# RPI_CM5_PINOUT.net
KiCad netlist of a schematic drawn in Altium Designer
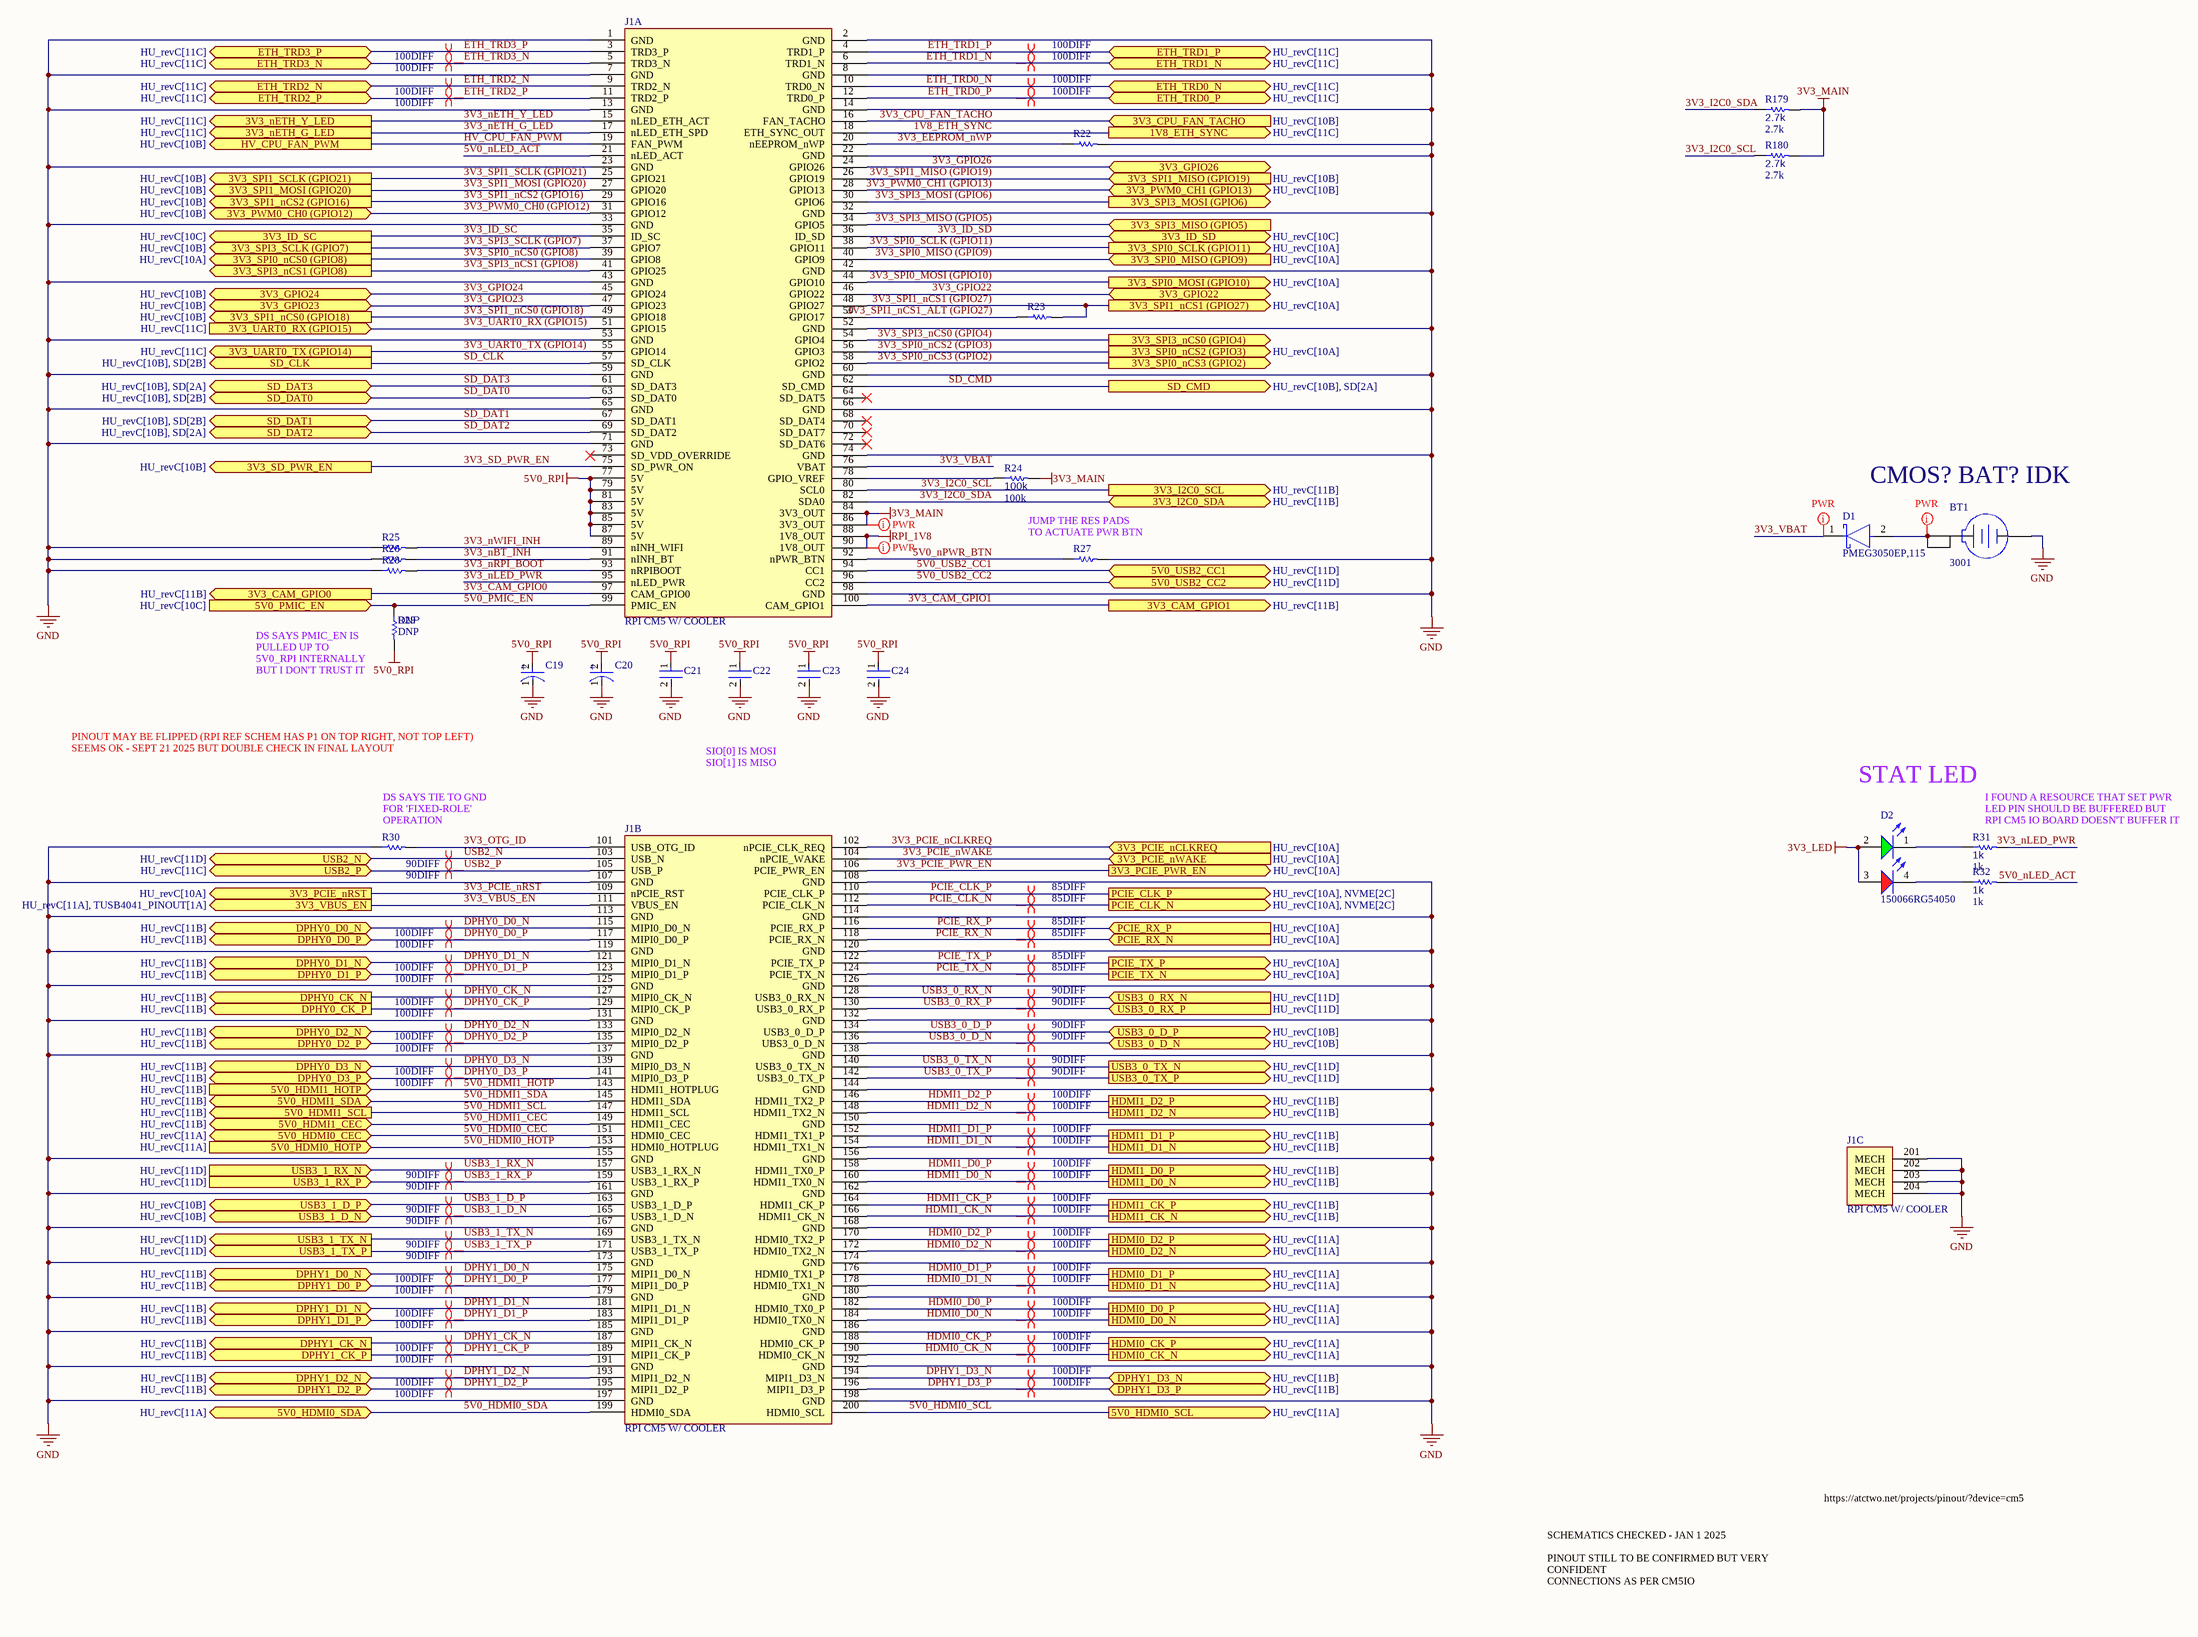
[diagram p0: RPI_CM5_PINOUT.SchDoc]

(export (version "E")
  (design (tool "Eeschema 10.0.6"))
  (components
    (comp (ref "BT1")
      (value "3001")
      (footprint "KSTN-3001_V")
      (description "Holder Battery Coin, 12 mm, 2-Pin THD, RoHS")
      (fields (field (name "MANUFACTURER") "Keystone"))
      (libsource (lib "Altium Content Vault") (part "BATTERY-HOLDER-COIN-3"))
    )
    (comp (ref "C19")
      (value "T491X107K025AT")
      (footprint "FP-T491X107K025AT-MFG")
      (description "CAP TANT 100UF 10% 25V 2917")
      (fields (field (name "TOLERANCE") "10%") (field (name "VOLTAGE") "25V"))
      (libsource (lib "Altium Content Vault") (part "cf48714ba7e38822c1575c7ec0b6d1f"))
    )
    (comp (ref "C20")
      (value "T491X107K025AT")
      (footprint "FP-T491X107K025AT-MFG")
      (description "CAP TANT 100UF 10% 25V 2917")
      (fields (field (name "TOLERANCE") "10%") (field (name "VOLTAGE") "25V"))
      (libsource (lib "Altium Content Vault") (part "cf48714ba7e38822c1575c7ec0b6d1f"))
    )
    (comp (ref "C21")
      (value "C3225X7R1H106M250AC")
      (footprint "FP-C3225-250-0_4-MFG")
      (description "Multilayer Ceramic Capacitors 10uF ±20% 50V X7R SMD 1210")
      (fields (field (name "TOLERANCE") "20%"))
      (libsource (lib "Altium Content Vault") (part "02cd4be3c70576c341d710602a673aa"))
    )
    (comp (ref "C22")
      (value "C3225X7R1H106M250AC")
      (footprint "FP-C3225-250-0_4-MFG")
      (description "Multilayer Ceramic Capacitors 10uF ±20% 50V X7R SMD 1210")
      (fields (field (name "TOLERANCE") "20%"))
      (libsource (lib "Altium Content Vault") (part "02cd4be3c70576c341d710602a673aa"))
    )
    (comp (ref "C23")
      (value "GRM21BR61E226ME44L")
      (footprint "FP-GRM21B-0_2-e0_2_0_7-IPC_B")
      (description "Chip Multilayer Ceramic Capacitors for General Purpose, 0805, 22uF, X5R, 15%, 20%, 25V")
      (fields (field (name "TOLERANCE") "20%") (field (name "VOLTAGE") "25V"))
      (libsource (lib "Altium Content Vault") (part "b4654b650e69147ec39a6b967a45e02"))
    )
    (comp (ref "C24")
      (value "GRM21BR61E226ME44L")
      (footprint "FP-GRM21B-0_2-e0_2_0_7-IPC_B")
      (description "Chip Multilayer Ceramic Capacitors for General Purpose, 0805, 22uF, X5R, 15%, 20%, 25V")
      (fields (field (name "TOLERANCE") "20%") (field (name "VOLTAGE") "25V"))
      (libsource (lib "Altium Content Vault") (part "b4654b650e69147ec39a6b967a45e02"))
    )
    (comp (ref "D1")
      (value "PMEG3050EP,115")
      (footprint "FP-SOD128-MFG")
      (description "DIODE SCHOTTKY 30V 5A SOD128")
      (libsource (lib "Altium Content Vault") (part "1d6ec82d83fb6aee721767c19dac4b9"))
    )
    (comp (ref "D2")
      (value "150066RG54050")
      (footprint "WL-SBCD_0606")
      (description "Led, Red/Grn, 180Mcd/230Mcd, 624Nm/525Nm Rohs Compliant: Yes")
      (fields (field (name "SOURCE") "rgled.SchLib"))
      (libsource (lib "Space Concordia") (part "CMP-004-00034-2"))
    )
    (comp (ref "J1")
      (value "RPI CM5 W/ COOLER")
      (footprint "RPI CM5 W_ COOLER-Footprint-1")
      (description "Mechanical placeholder for RPI CM5 w/ active cooler on it")
      (libsource (lib "Space Concordia") (part "10164227-1001A1RLF"))
    )
    (comp (ref "R22")
      (value "DNP")
      (footprint "RESC1005X40X25ML05T05")
      (description "READ THE NAME")
      (libsource (lib "Space Concordia") (part "CMP-009-00206-2"))
    )
    (comp (ref "R23")
      (value "DNP")
      (footprint "RESC1005X40X25ML05T05")
      (description "READ THE NAME")
      (libsource (lib "Space Concordia") (part "CMP-009-00206-2"))
    )
    (comp (ref "R24")
      (value "100k")
      (footprint "R0603B")
      (description "Resistor")
      (fields (field (name "ALTIUM_VALUE") "100k"))
      (libsource (lib "Space Concordia") (part "Resistor"))
    )
    (comp (ref "R25")
      (value "DNP")
      (footprint "RESC1005X40X25ML05T05")
      (description "READ THE NAME")
      (libsource (lib "Space Concordia") (part "CMP-009-00206-2"))
    )
    (comp (ref "R26")
      (value "DNP")
      (footprint "RESC1005X40X25ML05T05")
      (description "READ THE NAME")
      (libsource (lib "Space Concordia") (part "CMP-009-00206-2"))
    )
    (comp (ref "R27")
      (value "DNP")
      (footprint "RESC1005X40X25ML05T05")
      (description "READ THE NAME")
      (libsource (lib "Space Concordia") (part "CMP-009-00206-2"))
    )
    (comp (ref "R28")
      (value "DNP")
      (footprint "RESC1005X40X25ML05T05")
      (description "READ THE NAME")
      (libsource (lib "Space Concordia") (part "CMP-009-00206-2"))
    )
    (comp (ref "R29")
      (value "DNP")
      (footprint "R0603B")
      (description "Resistor")
      (fields (field (name "ALTIUM_VALUE") "DNP"))
      (libsource (lib "Space Concordia") (part "Resistor"))
    )
    (comp (ref "R30")
      (value "DNP")
      (footprint "RESC1005X40X25ML05T05")
      (description "READ THE NAME")
      (libsource (lib "Space Concordia") (part "CMP-009-00206-2"))
    )
    (comp (ref "R31")
      (value "1k")
      (footprint "R0603B")
      (description "Resistor")
      (fields (field (name "ALTIUM_VALUE") "1k"))
      (libsource (lib "Space Concordia") (part "Resistor"))
    )
    (comp (ref "R32")
      (value "1k")
      (footprint "R0603B")
      (description "Resistor")
      (fields (field (name "ALTIUM_VALUE") "1k"))
      (libsource (lib "Space Concordia") (part "Resistor"))
    )
    (comp (ref "R179")
      (value "2.7k")
      (footprint "R0603B")
      (description "Resistor")
      (fields (field (name "ALTIUM_VALUE") "2.7k"))
      (libsource (lib "Space Concordia") (part "Resistor"))
    )
    (comp (ref "R180")
      (value "2.7k")
      (footprint "R0603B")
      (description "Resistor")
      (fields (field (name "ALTIUM_VALUE") "2.7k"))
      (libsource (lib "Space Concordia") (part "Resistor"))
    )
  )
  (nets
    (net (code "1") (name "/1V8_ETH_SYNC") (class "Default")
      (node (ref "J1") (pin "18") (pinfunction "ETH_SYNC_OUT_18") (pintype "passive"))
    )
    (net (code "2") (name "/3V3_CAM_GPIO0") (class "Default")
      (node (ref "J1") (pin "97") (pinfunction "CAM_GPIO0_97") (pintype "passive"))
    )
    (net (code "3") (name "/3V3_CAM_GPIO1") (class "Default")
      (node (ref "J1") (pin "100") (pinfunction "CAM_GPIO1_100") (pintype "passive"))
    )
    (net (code "4") (name "/3V3_CPU_FAN_TACHO") (class "Default")
      (node (ref "J1") (pin "16") (pinfunction "FAN_TACHO_16") (pintype "passive"))
    )
    (net (code "5") (name "/3V3_EEPROM_nWP") (class "Default")
      (node (ref "J1") (pin "20") (pinfunction "nEEPROM_nWP_20") (pintype "passive"))
      (node (ref "R22") (pin "1") (pinfunction "1_1") (pintype "passive"))
    )
    (net (code "6") (name "/3V3_GPIO22") (class "Default")
      (node (ref "J1") (pin "46") (pinfunction "GPIO22_46") (pintype "passive"))
    )
    (net (code "7") (name "/3V3_GPIO23") (class "Default")
      (node (ref "J1") (pin "47") (pinfunction "GPIO23_47") (pintype "passive"))
    )
    (net (code "8") (name "/3V3_GPIO24") (class "Default")
      (node (ref "J1") (pin "45") (pinfunction "GPIO24_45") (pintype "passive"))
    )
    (net (code "9") (name "/3V3_GPIO26") (class "Default")
      (node (ref "J1") (pin "24") (pinfunction "GPIO26_24") (pintype "passive"))
    )
    (net (code "10") (name "/3V3_I2C0_SCL") (class "Default")
      (node (ref "J1") (pin "80") (pinfunction "SCL0_80") (pintype "passive"))
      (node (ref "R180") (pin "1") (pinfunction "1_1") (pintype "passive"))
    )
    (net (code "11") (name "/3V3_I2C0_SDA") (class "Default")
      (node (ref "J1") (pin "82") (pinfunction "SDA0_82") (pintype "passive"))
      (node (ref "R179") (pin "1") (pinfunction "1_1") (pintype "passive"))
    )
    (net (code "12") (name "/3V3_ID_SC") (class "Default")
      (node (ref "J1") (pin "35") (pinfunction "ID_SC_35") (pintype "passive"))
    )
    (net (code "13") (name "/3V3_ID_SD") (class "Default")
      (node (ref "J1") (pin "36") (pinfunction "ID_SD_36") (pintype "passive"))
    )
    (net (code "14") (name "/3V3_OTG_ID") (class "Default")
      (node (ref "J1") (pin "101") (pinfunction "USB_OTG_ID_101") (pintype "passive"))
      (node (ref "R30") (pin "2") (pinfunction "2_2") (pintype "passive"))
    )
    (net (code "15") (name "/3V3_PCIE_PWR_EN") (class "Default")
      (node (ref "J1") (pin "106") (pinfunction "PCIE_PWR_EN_106") (pintype "passive"))
    )
    (net (code "16") (name "/3V3_PCIE_nCLKREQ") (class "Default")
      (node (ref "J1") (pin "102") (pinfunction "nPCIE_CLK_REQ_102") (pintype "passive"))
    )
    (net (code "17") (name "/3V3_PCIE_nRST") (class "Default")
      (node (ref "J1") (pin "109") (pinfunction "nPCIE_RST_109") (pintype "passive"))
    )
    (net (code "18") (name "/3V3_PCIE_nWAKE") (class "Default")
      (node (ref "J1") (pin "104") (pinfunction "nPCIE_WAKE_104") (pintype "passive"))
    )
    (net (code "19") (name "/3V3_PWM0_CH0 (GPIO12)") (class "Default")
      (node (ref "J1") (pin "31") (pinfunction "GPIO12_31") (pintype "passive"))
    )
    (net (code "20") (name "/3V3_PWM0_CH1 (GPIO13)") (class "Default")
      (node (ref "J1") (pin "28") (pinfunction "GPIO13_28") (pintype "passive"))
    )
    (net (code "21") (name "/3V3_SD_PWR_EN") (class "Default")
      (node (ref "J1") (pin "75") (pinfunction "SD_PWR_ON_75") (pintype "passive"))
    )
    (net (code "22") (name "/3V3_SPI0_MISO (GPIO9)") (class "Default")
      (node (ref "J1") (pin "40") (pinfunction "GPIO9_40") (pintype "passive"))
    )
    (net (code "23") (name "/3V3_SPI0_MOSI (GPIO10)") (class "Default")
      (node (ref "J1") (pin "44") (pinfunction "GPIO10_44") (pintype "passive"))
    )
    (net (code "24") (name "/3V3_SPI0_SCLK (GPIO11)") (class "Default")
      (node (ref "J1") (pin "38") (pinfunction "GPIO11_38") (pintype "passive"))
    )
    (net (code "25") (name "/3V3_SPI0_nCS0 (GPIO8)") (class "Default")
      (node (ref "J1") (pin "39") (pinfunction "GPIO8_39") (pintype "passive"))
    )
    (net (code "26") (name "/3V3_SPI0_nCS2 (GPIO3)") (class "Default")
      (node (ref "J1") (pin "56") (pinfunction "GPIO3_56") (pintype "passive"))
    )
    (net (code "27") (name "/3V3_SPI0_nCS3 (GPIO2)") (class "Default")
      (node (ref "J1") (pin "58") (pinfunction "GPIO2_58") (pintype "passive"))
    )
    (net (code "28") (name "/3V3_SPI1_MISO (GPIO19)") (class "Default")
      (node (ref "J1") (pin "26") (pinfunction "GPIO19_26") (pintype "passive"))
    )
    (net (code "29") (name "/3V3_SPI1_MOSI (GPIO20)") (class "Default")
      (node (ref "J1") (pin "27") (pinfunction "GPIO20_27") (pintype "passive"))
    )
    (net (code "30") (name "/3V3_SPI1_SCLK (GPIO21)") (class "Default")
      (node (ref "J1") (pin "25") (pinfunction "GPIO21_25") (pintype "passive"))
    )
    (net (code "31") (name "/3V3_SPI1_nCS0 (GPIO18)") (class "Default")
      (node (ref "J1") (pin "49") (pinfunction "GPIO18_49") (pintype "passive"))
    )
    (net (code "32") (name "/3V3_SPI1_nCS1 (GPIO27)") (class "Default")
      (node (ref "J1") (pin "48") (pinfunction "GPIO27_48") (pintype "passive"))
      (node (ref "R23") (pin "2") (pinfunction "2_2") (pintype "passive"))
    )
    (net (code "33") (name "/3V3_SPI1_nCS1_ALT (GPIO27)") (class "Default")
      (node (ref "J1") (pin "50") (pinfunction "GPIO17_50") (pintype "passive"))
      (node (ref "R23") (pin "1") (pinfunction "1_1") (pintype "passive"))
    )
    (net (code "34") (name "/3V3_SPI1_nCS2 (GPIO16)") (class "Default")
      (node (ref "J1") (pin "29") (pinfunction "GPIO16_29") (pintype "passive"))
    )
    (net (code "35") (name "/3V3_SPI3_MISO (GPIO5)") (class "Default")
      (node (ref "J1") (pin "34") (pinfunction "GPIO5_34") (pintype "passive"))
    )
    (net (code "36") (name "/3V3_SPI3_MOSI (GPIO6)") (class "Default")
      (node (ref "J1") (pin "30") (pinfunction "GPIO6_30") (pintype "passive"))
    )
    (net (code "37") (name "/3V3_SPI3_SCLK (GPIO7)") (class "Default")
      (node (ref "J1") (pin "37") (pinfunction "GPIO7_37") (pintype "passive"))
    )
    (net (code "38") (name "/3V3_SPI3_nCS0 (GPIO4)") (class "Default")
      (node (ref "J1") (pin "54") (pinfunction "GPIO4_54") (pintype "passive"))
    )
    (net (code "39") (name "/3V3_SPI3_nCS1 (GPIO8)") (class "Default")
      (node (ref "J1") (pin "41") (pinfunction "GPIO25_41") (pintype "passive"))
    )
    (net (code "40") (name "/3V3_UART0_RX (GPIO15)") (class "Default")
      (node (ref "J1") (pin "51") (pinfunction "GPIO15_51") (pintype "passive"))
    )
    (net (code "41") (name "/3V3_UART0_TX (GPIO14)") (class "Default")
      (node (ref "J1") (pin "55") (pinfunction "GPIO14_55") (pintype "passive"))
    )
    (net (code "42") (name "/3V3_VBAT") (class "Default")
      (node (ref "D1") (pin "1") (pinfunction "C_1") (pintype "passive"))
      (node (ref "J1") (pin "76") (pinfunction "VBAT_76") (pintype "passive"))
    )
    (net (code "43") (name "/3V3_VBUS_EN") (class "Default")
      (node (ref "J1") (pin "111") (pinfunction "VBUS_EN_111") (pintype "passive"))
    )
    (net (code "44") (name "/3V3_nBT_INH") (class "Default")
      (node (ref "J1") (pin "91") (pinfunction "nINH_BT_91") (pintype "passive"))
      (node (ref "R26") (pin "2") (pinfunction "2_2") (pintype "passive"))
    )
    (net (code "45") (name "/3V3_nETH_G_LED") (class "Default")
      (node (ref "J1") (pin "17") (pinfunction "nLED_ETH_SPD_17") (pintype "passive"))
    )
    (net (code "46") (name "/3V3_nETH_Y_LED") (class "Default")
      (node (ref "J1") (pin "15") (pinfunction "nLED_ETH_ACT_15") (pintype "passive"))
    )
    (net (code "47") (name "/3V3_nLED_PWR") (class "Default")
      (node (ref "J1") (pin "95") (pinfunction "nLED_PWR_95") (pintype "passive"))
      (node (ref "R31") (pin "2") (pinfunction "2_2") (pintype "passive"))
    )
    (net (code "48") (name "/3V3_nRPI_BOOT") (class "Default")
      (node (ref "J1") (pin "93") (pinfunction "nRPIBOOT_93") (pintype "passive"))
      (node (ref "R28") (pin "2") (pinfunction "2_2") (pintype "passive"))
    )
    (net (code "49") (name "/3V3_nWIFI_INH") (class "Default")
      (node (ref "J1") (pin "89") (pinfunction "nINH_WIFI_89") (pintype "passive"))
      (node (ref "R25") (pin "2") (pinfunction "2_2") (pintype "passive"))
    )
    (net (code "50") (name "/5V0_HDMI0_CEC") (class "Default")
      (node (ref "J1") (pin "151") (pinfunction "HDMI0_CEC_151") (pintype "passive"))
    )
    (net (code "51") (name "/5V0_HDMI0_HOTP") (class "Default")
      (node (ref "J1") (pin "153") (pinfunction "HDMI0_HOTPLUG_153") (pintype "passive"))
    )
    (net (code "52") (name "/5V0_HDMI0_SCL") (class "Default")
      (node (ref "J1") (pin "200") (pinfunction "HDMI0_SCL_200") (pintype "passive"))
    )
    (net (code "53") (name "/5V0_HDMI0_SDA") (class "Default")
      (node (ref "J1") (pin "199") (pinfunction "HDMI0_SDA_199") (pintype "passive"))
    )
    (net (code "54") (name "/5V0_HDMI1_CEC") (class "Default")
      (node (ref "J1") (pin "149") (pinfunction "HDMI1_CEC_149") (pintype "passive"))
    )
    (net (code "55") (name "/5V0_HDMI1_HOTP") (class "Default")
      (node (ref "J1") (pin "143") (pinfunction "HDMI1_HOTPLUG_143") (pintype "passive"))
    )
    (net (code "56") (name "/5V0_HDMI1_SCL") (class "Default")
      (node (ref "J1") (pin "147") (pinfunction "HDMI1_SCL_147") (pintype "passive"))
    )
    (net (code "57") (name "/5V0_HDMI1_SDA") (class "Default")
      (node (ref "J1") (pin "145") (pinfunction "HDMI1_SDA_145") (pintype "passive"))
    )
    (net (code "58") (name "/5V0_PMIC_EN") (class "Default")
      (node (ref "J1") (pin "99") (pinfunction "PMIC_EN_99") (pintype "passive"))
      (node (ref "R29") (pin "1") (pinfunction "1_1") (pintype "passive"))
    )
    (net (code "59") (name "/5V0_USB2_CC1") (class "Default")
      (node (ref "J1") (pin "94") (pinfunction "CC1_94") (pintype "passive"))
    )
    (net (code "60") (name "/5V0_USB2_CC2") (class "Default")
      (node (ref "J1") (pin "96") (pinfunction "CC2_96") (pintype "passive"))
    )
    (net (code "61") (name "/5V0_nLED_ACT") (class "Default")
      (node (ref "J1") (pin "21") (pinfunction "nLED_ACT_21") (pintype "passive"))
      (node (ref "R32") (pin "2") (pinfunction "2_2") (pintype "passive"))
    )
    (net (code "62") (name "/5V0_nPWR_BTN") (class "Default")
      (node (ref "J1") (pin "92") (pinfunction "nPWR_BTN_92") (pintype "passive"))
      (node (ref "R27") (pin "1") (pinfunction "1_1") (pintype "passive"))
    )
    (net (code "63") (name "/DPHY0_CK_N") (class "Default")
      (node (ref "J1") (pin "127") (pinfunction "MIPI0_CK_N_127") (pintype "passive"))
    )
    (net (code "64") (name "/DPHY0_CK_P") (class "Default")
      (node (ref "J1") (pin "129") (pinfunction "MIPI0_CK_P_129") (pintype "passive"))
    )
    (net (code "65") (name "/DPHY0_D0_N") (class "Default")
      (node (ref "J1") (pin "115") (pinfunction "MIPI0_D0_N_115") (pintype "passive"))
    )
    (net (code "66") (name "/DPHY0_D0_P") (class "Default")
      (node (ref "J1") (pin "117") (pinfunction "MIPI0_D0_P_117") (pintype "passive"))
    )
    (net (code "67") (name "/DPHY0_D1_N") (class "Default")
      (node (ref "J1") (pin "121") (pinfunction "MIPI0_D1_N_121") (pintype "passive"))
    )
    (net (code "68") (name "/DPHY0_D1_P") (class "Default")
      (node (ref "J1") (pin "123") (pinfunction "MIPI0_D1_P_123") (pintype "passive"))
    )
    (net (code "69") (name "/DPHY0_D2_N") (class "Default")
      (node (ref "J1") (pin "133") (pinfunction "MIPI0_D2_N_133") (pintype "passive"))
    )
    (net (code "70") (name "/DPHY0_D2_P") (class "Default")
      (node (ref "J1") (pin "135") (pinfunction "MIPI0_D2_P_135") (pintype "passive"))
    )
    (net (code "71") (name "/DPHY0_D3_N") (class "Default")
      (node (ref "J1") (pin "139") (pinfunction "MIPI0_D3_N_139") (pintype "passive"))
    )
    (net (code "72") (name "/DPHY0_D3_P") (class "Default")
      (node (ref "J1") (pin "141") (pinfunction "MIPI0_D3_P_141") (pintype "passive"))
    )
    (net (code "73") (name "/DPHY1_CK_N") (class "Default")
      (node (ref "J1") (pin "187") (pinfunction "MIPI1_CK_N_187") (pintype "passive"))
    )
    (net (code "74") (name "/DPHY1_CK_P") (class "Default")
      (node (ref "J1") (pin "189") (pinfunction "MIPI1_CK_P_189") (pintype "passive"))
    )
    (net (code "75") (name "/DPHY1_D0_N") (class "Default")
      (node (ref "J1") (pin "175") (pinfunction "MIPI1_D0_N_175") (pintype "passive"))
    )
    (net (code "76") (name "/DPHY1_D0_P") (class "Default")
      (node (ref "J1") (pin "177") (pinfunction "MIPI1_D0_P_177") (pintype "passive"))
    )
    (net (code "77") (name "/DPHY1_D1_N") (class "Default")
      (node (ref "J1") (pin "181") (pinfunction "MIPI1_D1_N_181") (pintype "passive"))
    )
    (net (code "78") (name "/DPHY1_D1_P") (class "Default")
      (node (ref "J1") (pin "183") (pinfunction "MIPI1_D1_P_183") (pintype "passive"))
    )
    (net (code "79") (name "/DPHY1_D2_N") (class "Default")
      (node (ref "J1") (pin "193") (pinfunction "MIPI1_D2_N_193") (pintype "passive"))
    )
    (net (code "80") (name "/DPHY1_D2_P") (class "Default")
      (node (ref "J1") (pin "195") (pinfunction "MIPI1_D2_P_195") (pintype "passive"))
    )
    (net (code "81") (name "/DPHY1_D3_N") (class "Default")
      (node (ref "J1") (pin "194") (pinfunction "MIPI1_D3_N_194") (pintype "passive"))
    )
    (net (code "82") (name "/DPHY1_D3_P") (class "Default")
      (node (ref "J1") (pin "196") (pinfunction "MIPI1_D3_P_196") (pintype "passive"))
    )
    (net (code "83") (name "/ETH_TRD0_N") (class "Default")
      (node (ref "J1") (pin "10") (pinfunction "TRD0_N_10") (pintype "passive"))
    )
    (net (code "84") (name "/ETH_TRD0_P") (class "Default")
      (node (ref "J1") (pin "12") (pinfunction "TRD0_P_12") (pintype "passive"))
    )
    (net (code "85") (name "/ETH_TRD1_N") (class "Default")
      (node (ref "J1") (pin "6") (pinfunction "TRD1_N_6") (pintype "passive"))
    )
    (net (code "86") (name "/ETH_TRD1_P") (class "Default")
      (node (ref "J1") (pin "4") (pinfunction "TRD1_P_4") (pintype "passive"))
    )
    (net (code "87") (name "/ETH_TRD2_N") (class "Default")
      (node (ref "J1") (pin "9") (pinfunction "TRD2_N_9") (pintype "passive"))
    )
    (net (code "88") (name "/ETH_TRD2_P") (class "Default")
      (node (ref "J1") (pin "11") (pinfunction "TRD2_P_11") (pintype "passive"))
    )
    (net (code "89") (name "/ETH_TRD3_N") (class "Default")
      (node (ref "J1") (pin "5") (pinfunction "TRD3_N_5") (pintype "passive"))
    )
    (net (code "90") (name "/ETH_TRD3_P") (class "Default")
      (node (ref "J1") (pin "3") (pinfunction "TRD3_P_3") (pintype "passive"))
    )
    (net (code "91") (name "/HDMI0_CK_N") (class "Default")
      (node (ref "J1") (pin "190") (pinfunction "HDMI0_CK_N_190") (pintype "passive"))
    )
    (net (code "92") (name "/HDMI0_CK_P") (class "Default")
      (node (ref "J1") (pin "188") (pinfunction "HDMI0_CK_P_188") (pintype "passive"))
    )
    (net (code "93") (name "/HDMI0_D0_N") (class "Default")
      (node (ref "J1") (pin "184") (pinfunction "HDMI0_TX0_N_184") (pintype "passive"))
    )
    (net (code "94") (name "/HDMI0_D0_P") (class "Default")
      (node (ref "J1") (pin "182") (pinfunction "HDMI0_TX0_P_182") (pintype "passive"))
    )
    (net (code "95") (name "/HDMI0_D1_N") (class "Default")
      (node (ref "J1") (pin "178") (pinfunction "HDMI0_TX1_N_178") (pintype "passive"))
    )
    (net (code "96") (name "/HDMI0_D1_P") (class "Default")
      (node (ref "J1") (pin "176") (pinfunction "HDMI0_TX1_P_176") (pintype "passive"))
    )
    (net (code "97") (name "/HDMI0_D2_N") (class "Default")
      (node (ref "J1") (pin "172") (pinfunction "HDMI0_TX2_N_172") (pintype "passive"))
    )
    (net (code "98") (name "/HDMI0_D2_P") (class "Default")
      (node (ref "J1") (pin "170") (pinfunction "HDMI0_TX2_P_170") (pintype "passive"))
    )
    (net (code "99") (name "/HDMI1_CK_N") (class "Default")
      (node (ref "J1") (pin "166") (pinfunction "HDMI1_CK_N_166") (pintype "passive"))
    )
    (net (code "100") (name "/HDMI1_CK_P") (class "Default")
      (node (ref "J1") (pin "164") (pinfunction "HDMI1_CK_P_164") (pintype "passive"))
    )
    (net (code "101") (name "/HDMI1_D0_N") (class "Default")
      (node (ref "J1") (pin "160") (pinfunction "HDMI1_TX0_N_160") (pintype "passive"))
    )
    (net (code "102") (name "/HDMI1_D0_P") (class "Default")
      (node (ref "J1") (pin "158") (pinfunction "HDMI1_TX0_P_158") (pintype "passive"))
    )
    (net (code "103") (name "/HDMI1_D1_N") (class "Default")
      (node (ref "J1") (pin "154") (pinfunction "HDMI1_TX1_N_154") (pintype "passive"))
    )
    (net (code "104") (name "/HDMI1_D1_P") (class "Default")
      (node (ref "J1") (pin "152") (pinfunction "HDMI1_TX1_P_152") (pintype "passive"))
    )
    (net (code "105") (name "/HDMI1_D2_N") (class "Default")
      (node (ref "J1") (pin "148") (pinfunction "HDMI1_TX2_N_148") (pintype "passive"))
    )
    (net (code "106") (name "/HDMI1_D2_P") (class "Default")
      (node (ref "J1") (pin "146") (pinfunction "HDMI1_TX2_P_146") (pintype "passive"))
    )
    (net (code "107") (name "/HV_CPU_FAN_PWM") (class "Default")
      (node (ref "J1") (pin "19") (pinfunction "FAN_PWM_19") (pintype "passive"))
    )
    (net (code "108") (name "/PCIE_CLK_N") (class "Default")
      (node (ref "J1") (pin "112") (pinfunction "PCIE_CLK_N_112") (pintype "passive"))
    )
    (net (code "109") (name "/PCIE_CLK_P") (class "Default")
      (node (ref "J1") (pin "110") (pinfunction "PCIE_CLK_P_110") (pintype "passive"))
    )
    (net (code "110") (name "/PCIE_RX_N") (class "Default")
      (node (ref "J1") (pin "118") (pinfunction "PCIE_RX_N_118") (pintype "passive"))
    )
    (net (code "111") (name "/PCIE_RX_P") (class "Default")
      (node (ref "J1") (pin "116") (pinfunction "PCIE_RX_P_116") (pintype "passive"))
    )
    (net (code "112") (name "/PCIE_TX_N") (class "Default")
      (node (ref "J1") (pin "124") (pinfunction "PCIE_TX_N_124") (pintype "passive"))
    )
    (net (code "113") (name "/PCIE_TX_P") (class "Default")
      (node (ref "J1") (pin "122") (pinfunction "PCIE_TX_P_122") (pintype "passive"))
    )
    (net (code "114") (name "/SD_CLK") (class "Default")
      (node (ref "J1") (pin "57") (pinfunction "SD_CLK_57") (pintype "passive"))
    )
    (net (code "115") (name "/SD_CMD") (class "Default")
      (node (ref "J1") (pin "62") (pinfunction "SD_CMD_62") (pintype "passive"))
    )
    (net (code "116") (name "/SD_DAT0") (class "Default")
      (node (ref "J1") (pin "63") (pinfunction "SD_DAT0_63") (pintype "passive"))
    )
    (net (code "117") (name "/SD_DAT1") (class "Default")
      (node (ref "J1") (pin "67") (pinfunction "SD_DAT1_67") (pintype "passive"))
    )
    (net (code "118") (name "/SD_DAT2") (class "Default")
      (node (ref "J1") (pin "69") (pinfunction "SD_DAT2_69") (pintype "passive"))
    )
    (net (code "119") (name "/SD_DAT3") (class "Default")
      (node (ref "J1") (pin "61") (pinfunction "SD_DAT3_61") (pintype "passive"))
    )
    (net (code "120") (name "/USB2_N") (class "Default")
      (node (ref "J1") (pin "103") (pinfunction "USB_N_103") (pintype "passive"))
    )
    (net (code "121") (name "/USB2_P") (class "Default")
      (node (ref "J1") (pin "105") (pinfunction "USB_P_105") (pintype "passive"))
    )
    (net (code "122") (name "/USB3_0_D_N") (class "Default")
      (node (ref "J1") (pin "136") (pinfunction "UBS3_0_D_N_136") (pintype "passive"))
    )
    (net (code "123") (name "/USB3_0_D_P") (class "Default")
      (node (ref "J1") (pin "134") (pinfunction "USB3_0_D_P_134") (pintype "passive"))
    )
    (net (code "124") (name "/USB3_0_RX_N") (class "Default")
      (node (ref "J1") (pin "128") (pinfunction "USB3_0_RX_N_128") (pintype "passive"))
    )
    (net (code "125") (name "/USB3_0_RX_P") (class "Default")
      (node (ref "J1") (pin "130") (pinfunction "USB3_0_RX_P_130") (pintype "passive"))
    )
    (net (code "126") (name "/USB3_0_TX_N") (class "Default")
      (node (ref "J1") (pin "140") (pinfunction "USB3_0_TX_N_140") (pintype "passive"))
    )
    (net (code "127") (name "/USB3_0_TX_P") (class "Default")
      (node (ref "J1") (pin "142") (pinfunction "USB3_0_TX_P_142") (pintype "passive"))
    )
    (net (code "128") (name "/USB3_1_D_N") (class "Default")
      (node (ref "J1") (pin "165") (pinfunction "USB3_1_D_N_165") (pintype "passive"))
    )
    (net (code "129") (name "/USB3_1_D_P") (class "Default")
      (node (ref "J1") (pin "163") (pinfunction "USB3_1_D_P_163") (pintype "passive"))
    )
    (net (code "130") (name "/USB3_1_RX_N") (class "Default")
      (node (ref "J1") (pin "157") (pinfunction "USB3_1_RX_N_157") (pintype "passive"))
    )
    (net (code "131") (name "/USB3_1_RX_P") (class "Default")
      (node (ref "J1") (pin "159") (pinfunction "USB3_1_RX_P_159") (pintype "passive"))
    )
    (net (code "132") (name "/USB3_1_TX_N") (class "Default")
      (node (ref "J1") (pin "169") (pinfunction "USB3_1_TX_N_169") (pintype "passive"))
    )
    (net (code "133") (name "/USB3_1_TX_P") (class "Default")
      (node (ref "J1") (pin "171") (pinfunction "USB3_1_TX_P_171") (pintype "passive"))
    )
    (net (code "134") (name "3V3_LED") (class "Default")
      (node (ref "D2") (pin "2") (pinfunction "A_2") (pintype "passive"))
      (node (ref "D2") (pin "3") (pinfunction "A_3") (pintype "passive"))
    )
    (net (code "135") (name "3V3_MAIN") (class "Default")
      (node (ref "J1") (pin "84") (pinfunction "3V3_OUT_84") (pintype "passive"))
      (node (ref "J1") (pin "86") (pinfunction "3V3_OUT_86") (pintype "passive"))
      (node (ref "R179") (pin "2") (pinfunction "2_2") (pintype "passive"))
      (node (ref "R180") (pin "2") (pinfunction "2_2") (pintype "passive"))
      (node (ref "R24") (pin "2") (pinfunction "2_2") (pintype "passive"))
    )
    (net (code "136") (name "5V0_RPI") (class "Default")
      (node (ref "C19") (pin "2") (pinfunction "A_2") (pintype "passive"))
      (node (ref "C20") (pin "2") (pinfunction "A_2") (pintype "passive"))
      (node (ref "C21") (pin "1") (pinfunction "1_1") (pintype "passive"))
      (node (ref "C22") (pin "1") (pinfunction "1_1") (pintype "passive"))
      (node (ref "C23") (pin "1") (pinfunction "1_1") (pintype "passive"))
      (node (ref "C24") (pin "1") (pinfunction "1_1") (pintype "passive"))
      (node (ref "J1") (pin "77") (pinfunction "5V_77") (pintype "passive"))
      (node (ref "J1") (pin "79") (pinfunction "5V_79") (pintype "passive"))
      (node (ref "J1") (pin "81") (pinfunction "5V_81") (pintype "passive"))
      (node (ref "J1") (pin "83") (pinfunction "5V_83") (pintype "passive"))
      (node (ref "J1") (pin "85") (pinfunction "5V_85") (pintype "passive"))
      (node (ref "J1") (pin "87") (pinfunction "5V_87") (pintype "passive"))
      (node (ref "R29") (pin "2") (pinfunction "2_2") (pintype "passive"))
    )
    (net (code "137") (name "GND") (class "Default")
      (node (ref "BT1") (pin "3") (pinfunction "-_3") (pintype "passive"))
      (node (ref "C19") (pin "1") (pinfunction "C_1") (pintype "passive"))
      (node (ref "C20") (pin "1") (pinfunction "C_1") (pintype "passive"))
      (node (ref "C21") (pin "2") (pinfunction "2_2") (pintype "passive"))
      (node (ref "C22") (pin "2") (pinfunction "2_2") (pintype "passive"))
      (node (ref "C23") (pin "2") (pinfunction "2_2") (pintype "passive"))
      (node (ref "C24") (pin "2") (pinfunction "2_2") (pintype "passive"))
      (node (ref "J1") (pin "1") (pinfunction "GND_1") (pintype "passive"))
      (node (ref "J1") (pin "107") (pinfunction "GND_107") (pintype "passive"))
      (node (ref "J1") (pin "108") (pinfunction "GND_108") (pintype "passive"))
      (node (ref "J1") (pin "113") (pinfunction "GND_113") (pintype "passive"))
      (node (ref "J1") (pin "114") (pinfunction "GND_114") (pintype "passive"))
      (node (ref "J1") (pin "119") (pinfunction "GND_119") (pintype "passive"))
      (node (ref "J1") (pin "120") (pinfunction "GND_120") (pintype "passive"))
      (node (ref "J1") (pin "125") (pinfunction "GND_125") (pintype "passive"))
      (node (ref "J1") (pin "126") (pinfunction "GND_126") (pintype "passive"))
      (node (ref "J1") (pin "13") (pinfunction "GND_13") (pintype "passive"))
      (node (ref "J1") (pin "131") (pinfunction "GND_131") (pintype "passive"))
      (node (ref "J1") (pin "132") (pinfunction "GND_132") (pintype "passive"))
      (node (ref "J1") (pin "137") (pinfunction "GND_137") (pintype "passive"))
      (node (ref "J1") (pin "138") (pinfunction "GND_138") (pintype "passive"))
      (node (ref "J1") (pin "14") (pinfunction "GND_14") (pintype "passive"))
      (node (ref "J1") (pin "144") (pinfunction "GND_144") (pintype "passive"))
      (node (ref "J1") (pin "150") (pinfunction "GND_150") (pintype "passive"))
      (node (ref "J1") (pin "155") (pinfunction "GND_155") (pintype "passive"))
      (node (ref "J1") (pin "156") (pinfunction "GND_156") (pintype "passive"))
      (node (ref "J1") (pin "161") (pinfunction "GND_161") (pintype "passive"))
      (node (ref "J1") (pin "162") (pinfunction "GND_162") (pintype "passive"))
      (node (ref "J1") (pin "167") (pinfunction "GND_167") (pintype "passive"))
      (node (ref "J1") (pin "168") (pinfunction "GND_168") (pintype "passive"))
      (node (ref "J1") (pin "173") (pinfunction "GND_173") (pintype "passive"))
      (node (ref "J1") (pin "174") (pinfunction "GND_174") (pintype "passive"))
      (node (ref "J1") (pin "179") (pinfunction "GND_179") (pintype "passive"))
      (node (ref "J1") (pin "180") (pinfunction "GND_180") (pintype "passive"))
      (node (ref "J1") (pin "185") (pinfunction "GND_185") (pintype "passive"))
      (node (ref "J1") (pin "186") (pinfunction "GND_186") (pintype "passive"))
      (node (ref "J1") (pin "191") (pinfunction "GND_191") (pintype "passive"))
      (node (ref "J1") (pin "192") (pinfunction "GND_192") (pintype "passive"))
      (node (ref "J1") (pin "197") (pinfunction "GND_197") (pintype "passive"))
      (node (ref "J1") (pin "198") (pinfunction "GND_198") (pintype "passive"))
      (node (ref "J1") (pin "2") (pinfunction "GND_2") (pintype "passive"))
      (node (ref "J1") (pin "201") (pinfunction "MECH_201") (pintype "passive"))
      (node (ref "J1") (pin "202") (pinfunction "MECH_202") (pintype "passive"))
      (node (ref "J1") (pin "203") (pinfunction "MECH_203") (pintype "passive"))
      (node (ref "J1") (pin "204") (pinfunction "MECH_204") (pintype "passive"))
      (node (ref "J1") (pin "22") (pinfunction "GND_22") (pintype "passive"))
      (node (ref "J1") (pin "23") (pinfunction "GND_23") (pintype "passive"))
      (node (ref "J1") (pin "32") (pinfunction "GND_32") (pintype "passive"))
      (node (ref "J1") (pin "33") (pinfunction "GND_33") (pintype "passive"))
      (node (ref "J1") (pin "42") (pinfunction "GND_42") (pintype "passive"))
      (node (ref "J1") (pin "43") (pinfunction "GND_43") (pintype "passive"))
      (node (ref "J1") (pin "52") (pinfunction "GND_52") (pintype "passive"))
      (node (ref "J1") (pin "53") (pinfunction "GND_53") (pintype "passive"))
      (node (ref "J1") (pin "59") (pinfunction "GND_59") (pintype "passive"))
      (node (ref "J1") (pin "60") (pinfunction "GND_60") (pintype "passive"))
      (node (ref "J1") (pin "65") (pinfunction "GND_65") (pintype "passive"))
      (node (ref "J1") (pin "66") (pinfunction "GND_66") (pintype "passive"))
      (node (ref "J1") (pin "7") (pinfunction "GND_7") (pintype "passive"))
      (node (ref "J1") (pin "71") (pinfunction "GND_71") (pintype "passive"))
      (node (ref "J1") (pin "74") (pinfunction "GND_74") (pintype "passive"))
      (node (ref "J1") (pin "8") (pinfunction "GND_8") (pintype "passive"))
      (node (ref "J1") (pin "98") (pinfunction "GND_98") (pintype "passive"))
      (node (ref "R22") (pin "2") (pinfunction "2_2") (pintype "passive"))
      (node (ref "R25") (pin "1") (pinfunction "1_1") (pintype "passive"))
      (node (ref "R26") (pin "1") (pinfunction "1_1") (pintype "passive"))
      (node (ref "R27") (pin "2") (pinfunction "2_2") (pintype "passive"))
      (node (ref "R28") (pin "1") (pinfunction "1_1") (pintype "passive"))
      (node (ref "R30") (pin "1") (pinfunction "1_1") (pintype "passive"))
    )
    (net (code "138") (name "Net-(D1-A)") (class "Default")
      (node (ref "BT1") (pin "1") (pinfunction "+_1") (pintype "passive"))
      (node (ref "BT1") (pin "2") (pinfunction "+_2") (pintype "passive"))
      (node (ref "D1") (pin "2") (pinfunction "A_2") (pintype "passive"))
    )
    (net (code "139") (name "Net-(D2-K-Pad1)") (class "Default")
      (node (ref "D2") (pin "1") (pinfunction "K_1") (pintype "passive"))
      (node (ref "R31") (pin "1") (pinfunction "1_1") (pintype "passive"))
    )
    (net (code "140") (name "Net-(D2-K-Pad4)") (class "Default")
      (node (ref "D2") (pin "4") (pinfunction "K_4") (pintype "passive"))
      (node (ref "R32") (pin "1") (pinfunction "1_1") (pintype "passive"))
    )
    (net (code "141") (name "Net-(J1A-GPIO_VREF)") (class "Default")
      (node (ref "J1") (pin "78") (pinfunction "GPIO_VREF_78") (pintype "passive"))
      (node (ref "R24") (pin "1") (pinfunction "1_1") (pintype "passive"))
    )
    (net (code "142") (name "RPI_1V8") (class "Default")
      (node (ref "J1") (pin "88") (pinfunction "1V8_OUT_88") (pintype "passive"))
      (node (ref "J1") (pin "90") (pinfunction "1V8_OUT_90") (pintype "passive"))
    )
    (net (code "143") (name "unconnected-(J1A-SD_DAT4-Pad68)") (class "Default")
      (node (ref "J1") (pin "68") (pinfunction "SD_DAT4_68") (pintype "passive+no_connect"))
    )
    (net (code "144") (name "unconnected-(J1A-SD_DAT5-Pad64)") (class "Default")
      (node (ref "J1") (pin "64") (pinfunction "SD_DAT5_64") (pintype "passive+no_connect"))
    )
    (net (code "145") (name "unconnected-(J1A-SD_DAT6-Pad72)") (class "Default")
      (node (ref "J1") (pin "72") (pinfunction "SD_DAT6_72") (pintype "passive+no_connect"))
    )
    (net (code "146") (name "unconnected-(J1A-SD_DAT7-Pad70)") (class "Default")
      (node (ref "J1") (pin "70") (pinfunction "SD_DAT7_70") (pintype "passive+no_connect"))
    )
    (net (code "147") (name "unconnected-(J1A-SD_VDD_OVERRIDE-Pad73)") (class "Default")
      (node (ref "J1") (pin "73") (pinfunction "SD_VDD_OVERRIDE_73") (pintype "passive+no_connect"))
    )
  )
)
